# LCD.net
KiCad netlist of a schematic drawn in Altium Designer
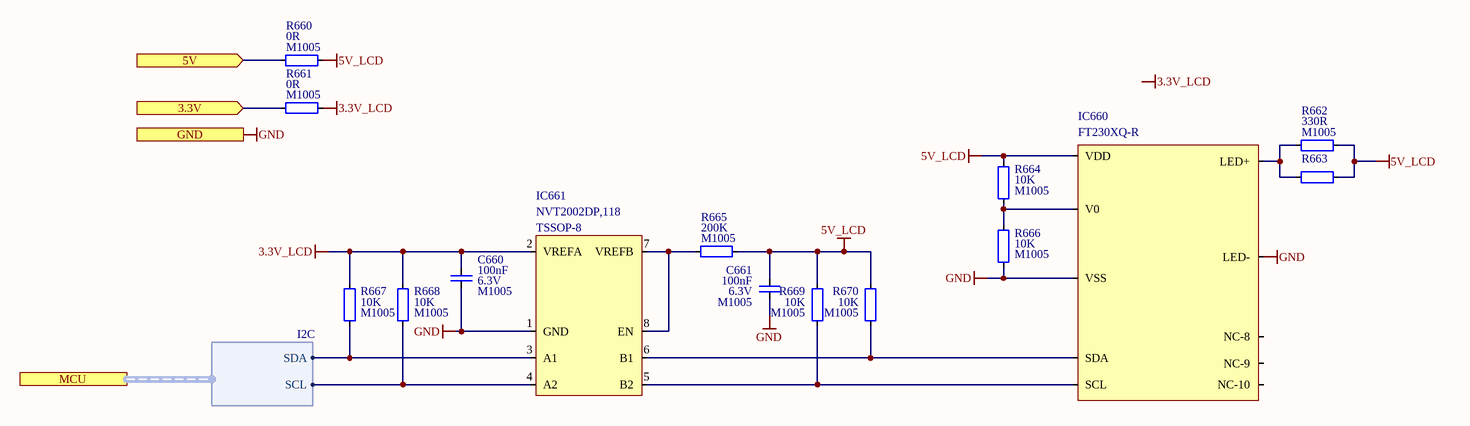
[diagram p0: LCD.SchDoc]

(export (version "E")
  (design (tool "Eeschema 10.0.6"))
  (components
    (comp (ref "C660")
      (value "100nF")
      (footprint "Capacitor_Ceramic_M1005_I0402")
      (description "Cap, Cer, 100nF, 6.3V, M1005")
      (fields
        (field (name "VOLTAGE") "6.3V")
        (field (name "MANUFACTURER PART NUMBER") "04026D104KAT4A")
        (field (name "MANUFACTURER") "Kyocera")
        (field (name "PACKAGE") "M1005")
      )
      (libsource (lib "Capacitor") (part "Capacitor_Ceramic"))
    )
    (comp (ref "C661")
      (value "100nF")
      (footprint "Capacitor_Ceramic_M1005_I0402")
      (description "Cap, Cer, 100nF, 6.3V, M1005")
      (fields
        (field (name "VOLTAGE") "6.3V")
        (field (name "MANUFACTURER PART NUMBER") "04026D104KAT4A")
        (field (name "MANUFACTURER") "Kyocera")
        (field (name "PACKAGE") "M1005")
      )
      (libsource (lib "Capacitor") (part "Capacitor_Ceramic"))
    )
    (comp (ref "IC660")
      (value "Orient, AMC0802BR-B-B6WTDW-I2C")
      (footprint "Orient, AMC0802BR-B-B6WTDW-I2C")
      (description "IC,Interface,FTDI,QFN16")
      (fields (field (name "MANUFACTURER") "FTDI") (field (name "MANUFACTURER PART NUMBER") "FT230XQ-R"))
      (libsource (lib "Module- LCD") (part "Orient, AMC0802BR-B-B6WTDW-I2C"))
    )
    (comp (ref "IC661")
      (value "Voltage Translator, I2C - Nxp, NVT2002DP")
      (footprint "TSSOP-8, Body 3mm, Pitch 0.65mm")
      (description "IC, Interface, I2C, TSSOP-8")
      (fields
        (field (name "MANUFACTURER") "Nxp")
        (field (name "MANUFACTURER PART NUMBER") "NVT2002DP,118")
        (field (name "PACKAGE") "TSSOP-8")
      )
      (libsource (lib "IC - Interface") (part "Voltage Translator, I2C - Nxp, NVT2002DP"))
    )
    (comp (ref "R660")
      (value "0R")
      (footprint "Resistor_Smd_M1005_I0402")
      (description "Res, 0R, M1005")
      (fields
        (field (name "MANUFACTURER") "Yageo")
        (field (name "MANUFACTURER PART NUMBER") "RC0402FR-070RL")
        (field (name "PACKAGE") "M1005")
      )
      (libsource (lib "Resistor") (part "Resistor"))
    )
    (comp (ref "R661")
      (value "0R")
      (footprint "Resistor_Smd_M1005_I0402")
      (description "Res, 0R, M1005")
      (fields
        (field (name "MANUFACTURER") "Yageo")
        (field (name "MANUFACTURER PART NUMBER") "RC0402FR-070RL")
        (field (name "PACKAGE") "M1005")
      )
      (libsource (lib "Resistor") (part "Resistor"))
    )
    (comp (ref "R662")
      (value "330R")
      (footprint "Resistor_Smd_M1005_I0402")
      (description "Res, 330R, 1%, M1005")
      (fields
        (field (name "TOLERANCE") "1%")
        (field (name "MANUFACTURER") "Yageo")
        (field (name "PACKAGE") "M1005")
      )
      (libsource (lib "Resistor") (part "Resistor"))
    )
    (comp (ref "R663")
      (value "Resistor")
      (footprint "Resistor_Smd_M1005_I0402")
      (description "Res, 330R, 1%, M1005")
      (fields (field (name "TOLERANCE") "1%") (field (name "MANUFACTURER") "Yageo"))
      (libsource (lib "Resistor") (part "Resistor"))
    )
    (comp (ref "R664")
      (value "10K")
      (footprint "Resistor_Smd_M1005_I0402")
      (description "Res, 10K, 1%, M1005")
      (fields
        (field (name "TOLERANCE") "1%")
        (field (name "MANUFACTURER") "Yageo")
        (field (name "PACKAGE") "M1005")
      )
      (libsource (lib "Resistor") (part "Resistor"))
    )
    (comp (ref "R665")
      (value "200K")
      (footprint "Resistor_Smd_M1005_I0402")
      (description "Res, 200K, 1%, M1005")
      (fields
        (field (name "TOLERANCE") "1%")
        (field (name "MANUFACTURER") "Yageo")
        (field (name "PACKAGE") "M1005")
      )
      (libsource (lib "Resistor") (part "Resistor"))
    )
    (comp (ref "R666")
      (value "10K")
      (footprint "Resistor_Smd_M1005_I0402")
      (description "Res, 10K, 1%, M1005")
      (fields
        (field (name "TOLERANCE") "1%")
        (field (name "MANUFACTURER") "Yageo")
        (field (name "PACKAGE") "M1005")
      )
      (libsource (lib "Resistor") (part "Resistor"))
    )
    (comp (ref "R667")
      (value "10K")
      (footprint "Resistor_Smd_M1005_I0402")
      (description "Res, 10K, 1%, M1005")
      (fields
        (field (name "TOLERANCE") "1%")
        (field (name "MANUFACTURER") "Yageo")
        (field (name "PACKAGE") "M1005")
      )
      (libsource (lib "Resistor") (part "Resistor"))
    )
    (comp (ref "R668")
      (value "10K")
      (footprint "Resistor_Smd_M1005_I0402")
      (description "Res, 10K, 1%, M1005")
      (fields
        (field (name "TOLERANCE") "1%")
        (field (name "MANUFACTURER") "Yageo")
        (field (name "PACKAGE") "M1005")
      )
      (libsource (lib "Resistor") (part "Resistor"))
    )
    (comp (ref "R669")
      (value "10K")
      (footprint "Resistor_Smd_M1005_I0402")
      (description "Res, 10K, 1%, M1005")
      (fields
        (field (name "TOLERANCE") "1%")
        (field (name "MANUFACTURER") "Yageo")
        (field (name "PACKAGE") "M1005")
      )
      (libsource (lib "Resistor") (part "Resistor"))
    )
    (comp (ref "R670")
      (value "10K")
      (footprint "Resistor_Smd_M1005_I0402")
      (description "Res, 10K, 1%, M1005")
      (fields
        (field (name "TOLERANCE") "1%")
        (field (name "MANUFACTURER") "Yageo")
        (field (name "PACKAGE") "M1005")
      )
      (libsource (lib "Resistor") (part "Resistor"))
    )
  )
  (nets
    (net (code "2") (name "/3.3V") (class "Default")
      (node (ref "R661") (pin "1") (pinfunction "1_1") (pintype "passive"))
    )
    (net (code "3") (name "/5V") (class "Default")
      (node (ref "R660") (pin "1") (pinfunction "1_1") (pintype "passive"))
    )
    (net (code "5") (name "3.3V_LCD") (class "Default")
      (node (ref "C660") (pin "1") (pinfunction "1_1") (pintype "passive"))
      (node (ref "IC661") (pin "2") (pinfunction "VREFA_2") (pintype "passive"))
      (node (ref "R661") (pin "2") (pinfunction "2_2") (pintype "passive"))
      (node (ref "R667") (pin "1") (pinfunction "1_1") (pintype "passive"))
      (node (ref "R668") (pin "1") (pinfunction "1_1") (pintype "passive"))
    )
    (net (code "6") (name "5V_LCD") (class "Default")
      (node (ref "C661") (pin "1") (pinfunction "1_1") (pintype "passive"))
      (node (ref "IC660") (pin "VDD") (pinfunction "VDD_VDD") (pintype "passive"))
      (node (ref "R660") (pin "2") (pinfunction "2_2") (pintype "passive"))
      (node (ref "R662") (pin "2") (pinfunction "2_2") (pintype "passive"))
      (node (ref "R663") (pin "2") (pinfunction "2_2") (pintype "passive"))
      (node (ref "R664") (pin "1") (pinfunction "1_1") (pintype "passive"))
      (node (ref "R665") (pin "2") (pinfunction "2_2") (pintype "passive"))
      (node (ref "R669") (pin "1") (pinfunction "1_1") (pintype "passive"))
      (node (ref "R670") (pin "1") (pinfunction "1_1") (pintype "passive"))
    )
    (net (code "7") (name "GND") (class "Default")
      (node (ref "C660") (pin "2") (pinfunction "2_2") (pintype "passive"))
      (node (ref "C661") (pin "2") (pinfunction "2_2") (pintype "passive"))
      (node (ref "IC660") (pin "LED-") (pinfunction "LED-_LED-") (pintype "passive"))
      (node (ref "IC660") (pin "VSS") (pinfunction "VSS_VSS") (pintype "passive"))
      (node (ref "IC661") (pin "1") (pinfunction "GND_1") (pintype "passive"))
      (node (ref "R666") (pin "2") (pinfunction "2_2") (pintype "passive"))
    )
    (net (code "8") (name "Net-(IC660-PadLED+)") (class "Default")
      (node (ref "IC660") (pin "LED+") (pinfunction "LED+_LED+") (pintype "passive"))
      (node (ref "R662") (pin "1") (pinfunction "1_1") (pintype "passive"))
      (node (ref "R663") (pin "1") (pinfunction "1_1") (pintype "passive"))
    )
    (net (code "9") (name "Net-(IC660-PadV0)") (class "Default")
      (node (ref "IC660") (pin "V0") (pinfunction "V0_V0") (pintype "passive"))
      (node (ref "R664") (pin "2") (pinfunction "2_2") (pintype "passive"))
      (node (ref "R666") (pin "1") (pinfunction "1_1") (pintype "passive"))
    )
    (net (code "10") (name "Net-(IC661-A1)") (class "Default")
      (node (ref "IC661") (pin "3") (pinfunction "A1_3") (pintype "passive"))
      (node (ref "R667") (pin "2") (pinfunction "2_2") (pintype "passive"))
    )
    (net (code "11") (name "Net-(IC661-A2)") (class "Default")
      (node (ref "IC661") (pin "4") (pinfunction "A2_4") (pintype "passive"))
      (node (ref "R668") (pin "2") (pinfunction "2_2") (pintype "passive"))
    )
    (net (code "12") (name "Net-(IC661-B1)") (class "Default")
      (node (ref "IC660") (pin "SDA") (pinfunction "SDA_SDA") (pintype "passive"))
      (node (ref "IC661") (pin "6") (pinfunction "B1_6") (pintype "passive"))
      (node (ref "R670") (pin "2") (pinfunction "2_2") (pintype "passive"))
    )
    (net (code "13") (name "Net-(IC661-B2)") (class "Default")
      (node (ref "IC660") (pin "SCL") (pinfunction "SCL_SCL") (pintype "passive"))
      (node (ref "IC661") (pin "5") (pinfunction "B2_5") (pintype "passive"))
      (node (ref "R669") (pin "2") (pinfunction "2_2") (pintype "passive"))
    )
    (net (code "14") (name "Net-(IC661-EN)") (class "Default")
      (node (ref "IC661") (pin "7") (pinfunction "VREFB_7") (pintype "passive"))
      (node (ref "IC661") (pin "8") (pinfunction "EN_8") (pintype "passive"))
      (node (ref "R665") (pin "1") (pinfunction "1_1") (pintype "passive"))
    )
    (net (code "15") (name "unconnected-(IC660-PadNC-8)") (class "Default")
      (node (ref "IC660") (pin "NC-8") (pinfunction "NC-8_NC-8") (pintype "passive"))
    )
    (net (code "16") (name "unconnected-(IC660-PadNC-9)") (class "Default")
      (node (ref "IC660") (pin "NC-9") (pinfunction "NC-9_NC-9") (pintype "passive"))
    )
    (net (code "17") (name "unconnected-(IC660-PadNC-10)") (class "Default")
      (node (ref "IC660") (pin "NC-10") (pinfunction "NC-10_NC-10") (pintype "passive"))
    )
  )
)
